# PadaukPMS171BTestBoard.net
KiCad netlist of a schematic drawn in Altium Designer
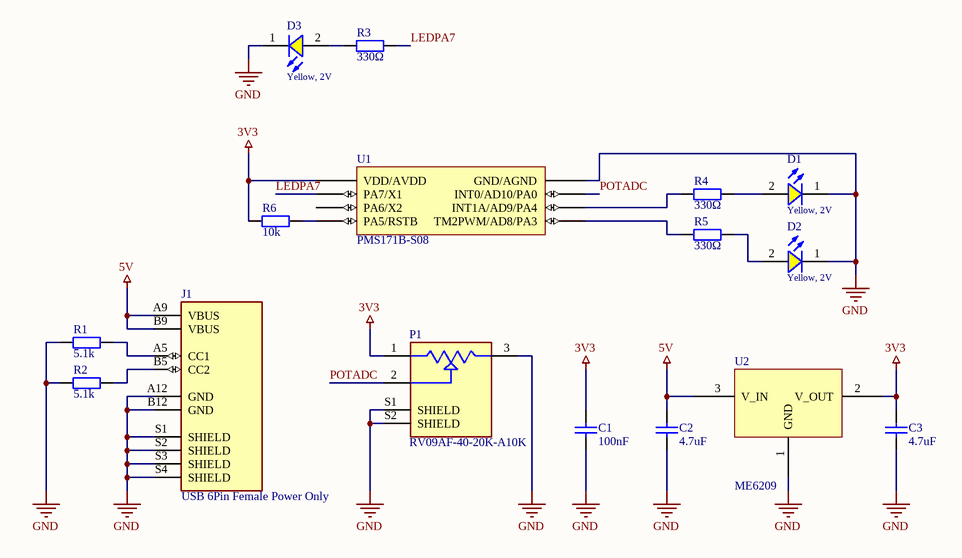
[diagram p0: PadaukPMS171BTestBoard.SchDoc]

(export (version "E")
  (design (tool "Eeschema 10.0.6"))
  (components
    (comp (ref "C1")
      (value "100nF")
      (footprint "WCAP-CSGP_0805_H=0.8mm_Reflow")
      (description "WCAP-CSGP General Purpose Ceramic Capacitors, size 0805, 1nF, +/-5%, 16VDC")
      (fields (field (name "PART NUMBER") "885012007021") (field (name "PUBLISHER") "Wurth Elektronik"))
      (libsource (lib "Altium_WCAP-CSGP (rev19a)") (part "885012007021"))
    )
    (comp (ref "C2")
      (value "4.7uF")
      (footprint "WCAP-CSGP_0805_H=0.8mm_Reflow")
      (description "WCAP-CSGP General Purpose Ceramic Capacitors, size 0805, 1nF, +/-5%, 16VDC")
      (fields (field (name "PART NUMBER") "885012007021") (field (name "PUBLISHER") "Wurth Elektronik"))
      (libsource (lib "Altium_WCAP-CSGP (rev19a)") (part "885012007021"))
    )
    (comp (ref "C3")
      (value "4.7uF")
      (footprint "WCAP-CSGP_0805_H=0.8mm_Reflow")
      (description "WCAP-CSGP General Purpose Ceramic Capacitors, size 0805, 1nF, +/-5%, 16VDC")
      (fields (field (name "PART NUMBER") "885012007021") (field (name "PUBLISHER") "Wurth Elektronik"))
      (libsource (lib "Altium_WCAP-CSGP (rev19a)") (part "885012007021"))
    )
    (comp (ref "D1")
      (value "Yellow, 2V")
      (footprint "WL-SMCW_0603_H=0.7mm")
      (description "WL-SMCW SMT Mono-color Chip LED Waterclear, size 0603, Yellow, 2V, 140deg")
      (fields (field (name "PART NUMBER") "150060YS75000") (field (name "PUBLISHER") "Wurth Elektronik"))
      (libsource (lib "150060BS75000_Altium_WL-SMCW_rev20a") (part "150060YS75000"))
    )
    (comp (ref "D2")
      (value "Yellow, 2V")
      (footprint "WL-SMCW_0603_H=0.7mm")
      (description "WL-SMCW SMT Mono-color Chip LED Waterclear, size 0603, Yellow, 2V, 140deg")
      (fields (field (name "PART NUMBER") "150060YS75000") (field (name "PUBLISHER") "Wurth Elektronik"))
      (libsource (lib "150060BS75000_Altium_WL-SMCW_rev20a") (part "150060YS75000"))
    )
    (comp (ref "D3")
      (value "Yellow, 2V")
      (footprint "WL-SMCW_0603_H=0.7mm")
      (description "WL-SMCW SMT Mono-color Chip LED Waterclear, size 0603, Yellow, 2V, 140deg")
      (fields (field (name "PART NUMBER") "150060YS75000") (field (name "PUBLISHER") "Wurth Elektronik"))
      (libsource (lib "150060BS75000_Altium_WL-SMCW_rev20a") (part "150060YS75000"))
    )
    (comp (ref "J1")
      (value "USB 6Pin Female Power Only")
      (footprint "GCT_USB4125-GF-A_REVA2")
      (fields (field (name "MP") "USB4125-GF-A_REVA2"))
      (libsource (lib "USBC_6P_Female") (part "USB4125-GF-A_REVA2"))
    )
    (comp (ref "P1")
      (value "RV09AF-40-20K-A10K")
      (footprint "PTV09A-4025F-B103")
      (description "PC Mount Black Shaft Potentiometers Audio 9mm 10K")
      (fields (field (name "MF") "Alpha Taiwan"))
      (libsource (lib "PTV09A-Potentiometer") (part "RV09AF-40-20K-A10K"))
    )
    (comp (ref "R1")
      (value "5.1k")
      (footprint "WRIS-PSMB_0805_H=0.22mm")
      (description "WRIS-PSMB Metal Plate Resistors, size 0805, 10mOhm, +/-1%, 0.5W")
      (fields (field (name "PART NUMBER") "580060720008") (field (name "PUBLISHER") "Wurth Elektronik"))
      (libsource (lib "Altium_WRIS-PSMB (rev19a)") (part "580060720008"))
    )
    (comp (ref "R2")
      (value "5.1k")
      (footprint "WRIS-PSMB_0805_H=0.22mm")
      (description "WRIS-PSMB Metal Plate Resistors, size 0805, 10mOhm, +/-1%, 0.5W")
      (fields (field (name "PART NUMBER") "580060720008") (field (name "PUBLISHER") "Wurth Elektronik"))
      (libsource (lib "Altium_WRIS-PSMB (rev19a)") (part "580060720008"))
    )
    (comp (ref "R3")
      (value "330Ω")
      (footprint "WRIS-PSMB_0805_H=0.22mm")
      (description "WRIS-PSMB Metal Plate Resistors, size 0805, 10mOhm, +/-1%, 0.5W")
      (fields (field (name "PART NUMBER") "580060720008") (field (name "PUBLISHER") "Wurth Elektronik"))
      (libsource (lib "") (part "580060720008_1"))
    )
    (comp (ref "R4")
      (value "330Ω")
      (footprint "WRIS-PSMB_0805_H=0.22mm")
      (description "WRIS-PSMB Metal Plate Resistors, size 0805, 10mOhm, +/-1%, 0.5W")
      (fields (field (name "PART NUMBER") "580060720008") (field (name "PUBLISHER") "Wurth Elektronik"))
      (libsource (lib "") (part "580060720008_1"))
    )
    (comp (ref "R5")
      (value "330Ω")
      (footprint "WRIS-PSMB_0805_H=0.22mm")
      (description "WRIS-PSMB Metal Plate Resistors, size 0805, 10mOhm, +/-1%, 0.5W")
      (fields (field (name "PART NUMBER") "580060720008") (field (name "PUBLISHER") "Wurth Elektronik"))
      (libsource (lib "") (part "580060720008_1"))
    )
    (comp (ref "R6")
      (value "10k")
      (footprint "WRIS-PSMB_0805_H=0.22mm")
      (description "WRIS-PSMB Metal Plate Resistors, size 0805, 10mOhm, +/-1%, 0.5W")
      (fields (field (name "PART NUMBER") "580060720008") (field (name "PUBLISHER") "Wurth Elektronik"))
      (libsource (lib "Altium_WRIS-PSMB (rev19a)") (part "580060720008"))
    )
    (comp (ref "U1")
      (value "PMS171B-S08")
      (footprint "PMS171B-S08")
      (libsource (lib "PMS171B-S08") (part "PMS171B-S08"))
    )
    (comp (ref "U2")
      (value "ME6209")
      (footprint "SOT95P285X150-3N")
      (libsource (lib "ME6209") (part "ME6209"))
    )
  )
  (nets
    (net (code "1") (name "/LEDPA7") (class "Default")
      (node (ref "R3") (pin "1") (pinfunction "1_1") (pintype "passive"))
      (node (ref "U1") (pin "2") (pinfunction "PA7/X1_2") (pintype "bidirectional"))
    )
    (net (code "2") (name "/POTADC") (class "Default")
      (node (ref "P1") (pin "2") (pinfunction "2_2") (pintype "passive"))
      (node (ref "U1") (pin "7") (pinfunction "INT0/AD10/PA0_7") (pintype "bidirectional"))
    )
    (net (code "3") (name "3V3") (class "Default")
      (node (ref "C1") (pin "2") (pinfunction "2_2") (pintype "passive"))
      (node (ref "C3") (pin "2") (pinfunction "2_2") (pintype "passive"))
      (node (ref "P1") (pin "1") (pinfunction "1_1") (pintype "passive"))
      (node (ref "R6") (pin "1") (pinfunction "1_1") (pintype "passive"))
      (node (ref "U1") (pin "1") (pinfunction "VDD/AVDD_1") (pintype "power_in"))
      (node (ref "U2") (pin "2") (pinfunction "V_OUT_2") (pintype "passive"))
    )
    (net (code "4") (name "5V") (class "Default")
      (node (ref "C2") (pin "2") (pinfunction "2_2") (pintype "passive"))
      (node (ref "J1") (pin "A9") (pinfunction "VBUS_A9") (pintype "power_in"))
      (node (ref "J1") (pin "B9") (pinfunction "VBUS_B9") (pintype "power_in"))
      (node (ref "U2") (pin "3") (pinfunction "V_IN_3") (pintype "passive"))
    )
    (net (code "5") (name "GND") (class "Default")
      (node (ref "C1") (pin "1") (pinfunction "1_1") (pintype "passive"))
      (node (ref "C2") (pin "1") (pinfunction "1_1") (pintype "passive"))
      (node (ref "C3") (pin "1") (pinfunction "1_1") (pintype "passive"))
      (node (ref "D1") (pin "1") (pinfunction "K_1") (pintype "passive"))
      (node (ref "D2") (pin "1") (pinfunction "K_1") (pintype "passive"))
      (node (ref "D3") (pin "1") (pinfunction "K_1") (pintype "passive"))
      (node (ref "J1") (pin "A12") (pinfunction "GND_A12") (pintype "power_in"))
      (node (ref "J1") (pin "B12") (pinfunction "GND_B12") (pintype "power_in"))
      (node (ref "J1") (pin "S1") (pinfunction "SHIELD_S1") (pintype "passive"))
      (node (ref "J1") (pin "S2") (pinfunction "SHIELD_S2") (pintype "passive"))
      (node (ref "J1") (pin "S3") (pinfunction "SHIELD_S3") (pintype "passive"))
      (node (ref "J1") (pin "S4") (pinfunction "SHIELD_S4") (pintype "passive"))
      (node (ref "P1") (pin "3") (pinfunction "3_3") (pintype "passive"))
      (node (ref "P1") (pin "S1") (pinfunction "SHIELD_S1") (pintype "passive"))
      (node (ref "P1") (pin "S2") (pinfunction "SHIELD_S2") (pintype "passive"))
      (node (ref "R1") (pin "1") (pinfunction "1_1") (pintype "passive"))
      (node (ref "R2") (pin "1") (pinfunction "1_1") (pintype "passive"))
      (node (ref "U1") (pin "8") (pinfunction "GND/AGND_8") (pintype "passive"))
      (node (ref "U2") (pin "1") (pinfunction "GND_1") (pintype "passive"))
    )
    (net (code "6") (name "Net-(D1-A)") (class "Default")
      (node (ref "D1") (pin "2") (pinfunction "A_2") (pintype "passive"))
      (node (ref "R4") (pin "1") (pinfunction "1_1") (pintype "passive"))
    )
    (net (code "7") (name "Net-(D2-A)") (class "Default")
      (node (ref "D2") (pin "2") (pinfunction "A_2") (pintype "passive"))
      (node (ref "R5") (pin "1") (pinfunction "1_1") (pintype "passive"))
    )
    (net (code "8") (name "Net-(D3-A)") (class "Default")
      (node (ref "D3") (pin "2") (pinfunction "A_2") (pintype "passive"))
      (node (ref "R3") (pin "2") (pinfunction "2_2") (pintype "passive"))
    )
    (net (code "9") (name "Net-(J1-CC1)") (class "Default")
      (node (ref "J1") (pin "A5") (pinfunction "CC1_A5") (pintype "bidirectional"))
      (node (ref "R1") (pin "2") (pinfunction "2_2") (pintype "passive"))
    )
    (net (code "10") (name "Net-(J1-CC2)") (class "Default")
      (node (ref "J1") (pin "B5") (pinfunction "CC2_B5") (pintype "bidirectional"))
      (node (ref "R2") (pin "2") (pinfunction "2_2") (pintype "passive"))
    )
    (net (code "11") (name "Net-(U1-INT1A{slash}AD9{slash}PA4)") (class "Default")
      (node (ref "R4") (pin "2") (pinfunction "2_2") (pintype "passive"))
      (node (ref "U1") (pin "6") (pinfunction "INT1A/AD9/PA4_6") (pintype "bidirectional"))
    )
    (net (code "12") (name "Net-(U1-PA5{slash}RSTB)") (class "Default")
      (node (ref "R6") (pin "2") (pinfunction "2_2") (pintype "passive"))
      (node (ref "U1") (pin "4") (pinfunction "PA5/RSTB_4") (pintype "bidirectional"))
    )
    (net (code "13") (name "Net-(U1-TM2PWM{slash}AD8{slash}PA3)") (class "Default")
      (node (ref "R5") (pin "2") (pinfunction "2_2") (pintype "passive"))
      (node (ref "U1") (pin "5") (pinfunction "TM2PWM/AD8/PA3_5") (pintype "bidirectional"))
    )
    (net (code "14") (name "unconnected-(U1-PA6{slash}X2-Pad3)") (class "Default")
      (node (ref "U1") (pin "3") (pinfunction "PA6/X2_3") (pintype "bidirectional"))
    )
  )
)
